# slapcie.net
KiCad netlist of a schematic drawn in Altium Designer
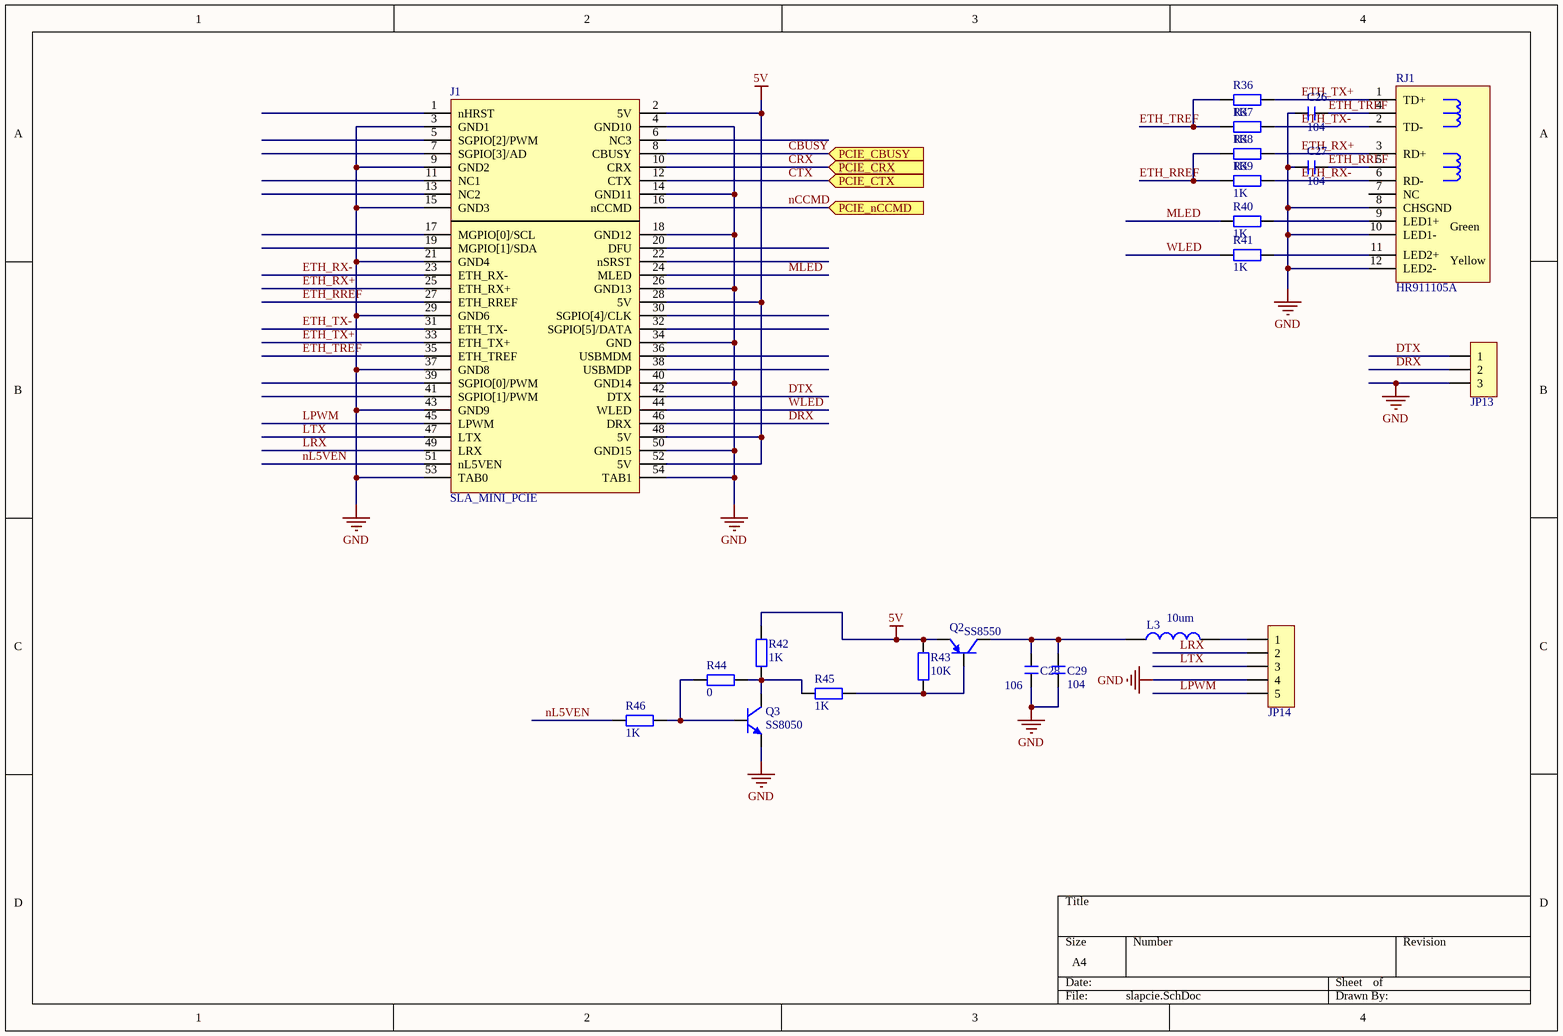
[diagram p0: slapcie.SchDoc]

(export (version "E")
  (design (tool "Eeschema 10.0.6"))
  (components
    (comp (ref "C26")
      (value "104")
      (footprint "C 0603_L")
      (description "无极性贴片电容")
      (fields (field (name "版权归属") "源创客"))
      (libsource (lib "3.1   - 电阻-电容-电感") (part "C"))
    )
    (comp (ref "C27")
      (value "104")
      (footprint "C 0603_L")
      (description "无极性贴片电容")
      (fields (field (name "版权归属") "源创客"))
      (libsource (lib "3.1   - 电阻-电容-电感") (part "C"))
    )
    (comp (ref "C28")
      (value "106")
      (footprint "C 0603_L")
      (description "无极性贴片电容")
      (fields (field (name "版权归属") "源创客"))
      (libsource (lib "3.1   - 电阻-电容-电感") (part "C"))
    )
    (comp (ref "C29")
      (value "104")
      (footprint "C 0603_L")
      (description "无极性贴片电容")
      (fields (field (name "版权归属") "源创客"))
      (libsource (lib "3.1   - 电阻-电容-电感") (part "C"))
    )
    (comp (ref "J1")
      (value "SLA_MINI_PCIE")
      (footprint "MINI_PCIE")
      (libsource (lib "元件库合集") (part "SLA_PCIE"))
    )
    (comp (ref "JP13")
      (value "HDR-1X3")
      (footprint "XH2.54-LI-3P")
      (description "3P接插件")
      (fields (field (name "版权归属") "源创客"))
      (libsource (lib "4.5   - 接插件-脚距2.54") (part "Header 3"))
    )
    (comp (ref "JP14")
      (value "HDR-1X5")
      (footprint "XH2.54-WI-5P")
      (description "5P接插件")
      (fields (field (name "版权归属") "源创客"))
      (libsource (lib "4.5   - 接插件-脚距2.54") (part "Header 5"))
    )
    (comp (ref "L3")
      (value "10um")
      (footprint "L 0805")
      (description "小功率贴片电感")
      (fields (field (name "版权归属") "源创客"))
      (libsource (lib "电阻-电容-电感") (part "L"))
    )
    (comp (ref "Q2")
      (value "SS8550")
      (footprint "SOT23-3N")
      (description "高频放大-PNP型")
      (fields (field (name "版权归属") "源创客"))
      (libsource (lib "三极管") (part "8550-SMD"))
    )
    (comp (ref "Q3")
      (value "SS8050")
      (footprint "SOT23-3N")
      (description "高频放大-NPN型")
      (fields (field (name "版权归属") "源创客"))
      (libsource (lib "三极管") (part "8050-SMD"))
    )
    (comp (ref "R36")
      (value "1K")
      (footprint "R 0603_L")
      (description "贴片电阻")
      (fields (field (name "版权归属") "源创客"))
      (libsource (lib "3.1   - 电阻-电容-电感") (part "R"))
    )
    (comp (ref "R37")
      (value "1K")
      (footprint "R 0603_L")
      (description "贴片电阻")
      (fields (field (name "版权归属") "源创客"))
      (libsource (lib "3.1   - 电阻-电容-电感") (part "R"))
    )
    (comp (ref "R38")
      (value "1K")
      (footprint "R 0603_L")
      (description "贴片电阻")
      (fields (field (name "版权归属") "源创客"))
      (libsource (lib "3.1   - 电阻-电容-电感") (part "R"))
    )
    (comp (ref "R39")
      (value "1K")
      (footprint "R 0603_L")
      (description "贴片电阻")
      (fields (field (name "版权归属") "源创客"))
      (libsource (lib "3.1   - 电阻-电容-电感") (part "R"))
    )
    (comp (ref "R40")
      (value "1K")
      (footprint "R 0603_L")
      (description "贴片电阻")
      (fields (field (name "版权归属") "源创客"))
      (libsource (lib "3.1   - 电阻-电容-电感") (part "R"))
    )
    (comp (ref "R41")
      (value "1K")
      (footprint "R 0603_L")
      (description "贴片电阻")
      (fields (field (name "版权归属") "源创客"))
      (libsource (lib "3.1   - 电阻-电容-电感") (part "R"))
    )
    (comp (ref "R42")
      (value "1K")
      (footprint "R 0603_L")
      (description "贴片电阻")
      (fields (field (name "版权归属") "源创客"))
      (libsource (lib "3.1   - 电阻-电容-电感") (part "R"))
    )
    (comp (ref "R43")
      (value "10K")
      (footprint "R 0603_L")
      (description "贴片电阻")
      (fields (field (name "版权归属") "源创客"))
      (libsource (lib "3.1   - 电阻-电容-电感") (part "R"))
    )
    (comp (ref "R44")
      (value "0")
      (footprint "R 0603_L")
      (description "贴片电阻")
      (fields (field (name "版权归属") "源创客"))
      (libsource (lib "3.1   - 电阻-电容-电感") (part "R"))
    )
    (comp (ref "R45")
      (value "1K")
      (footprint "R 0603_L")
      (description "贴片电阻")
      (fields (field (name "版权归属") "源创客"))
      (libsource (lib "3.1   - 电阻-电容-电感") (part "R"))
    )
    (comp (ref "R46")
      (value "1K")
      (footprint "R 0603_L")
      (description "贴片电阻")
      (fields (field (name "版权归属") "源创客"))
      (libsource (lib "3.1   - 电阻-电容-电感") (part "R"))
    )
    (comp (ref "RJ1")
      (value "HR911105A")
      (footprint "RJ-45A12")
      (description "带灯以太网接口")
      (fields (field (name "版权归属") "源创客"))
      (libsource (lib "接口类") (part "HR911105A"))
    )
  )
  (nets
    (net (code "1") (name "/CBUSY") (class "Default")
      (node (ref "J1") (pin "8") (pinfunction "CBUSY_8") (pintype "passive"))
    )
    (net (code "2") (name "/CRX") (class "Default")
      (node (ref "J1") (pin "10") (pinfunction "CRX_10") (pintype "passive"))
    )
    (net (code "3") (name "/CTX") (class "Default")
      (node (ref "J1") (pin "12") (pinfunction "CTX_12") (pintype "passive"))
    )
    (net (code "4") (name "/DRX") (class "Default")
      (node (ref "J1") (pin "46") (pinfunction "DRX_46") (pintype "passive"))
      (node (ref "JP13") (pin "2") (pinfunction "2_2") (pintype "passive"))
    )
    (net (code "5") (name "/DTX") (class "Default")
      (node (ref "J1") (pin "42") (pinfunction "DTX_42") (pintype "passive"))
      (node (ref "JP13") (pin "1") (pinfunction "1_1") (pintype "passive"))
    )
    (net (code "6") (name "/ETH_RREF") (class "Default")
      (node (ref "C27") (pin "2") (pinfunction "2_2") (pintype "passive"))
      (node (ref "J1") (pin "27") (pinfunction "ETH_RREF_27") (pintype "passive"))
      (node (ref "R38") (pin "1") (pinfunction "1_1") (pintype "passive"))
      (node (ref "R39") (pin "1") (pinfunction "1_1") (pintype "passive"))
      (node (ref "RJ1") (pin "5") (pintype "passive"))
    )
    (net (code "7") (name "/ETH_RX+") (class "Default")
      (node (ref "J1") (pin "25") (pinfunction "ETH_RX+_25") (pintype "passive"))
      (node (ref "R38") (pin "2") (pinfunction "2_2") (pintype "passive"))
      (node (ref "RJ1") (pin "3") (pinfunction "RD+_3") (pintype "passive"))
    )
    (net (code "8") (name "/ETH_RX-") (class "Default")
      (node (ref "J1") (pin "23") (pinfunction "ETH_RX-_23") (pintype "passive"))
      (node (ref "R39") (pin "2") (pinfunction "2_2") (pintype "passive"))
      (node (ref "RJ1") (pin "6") (pinfunction "RD-_6") (pintype "passive"))
    )
    (net (code "9") (name "/ETH_TREF") (class "Default")
      (node (ref "C26") (pin "2") (pinfunction "2_2") (pintype "passive"))
      (node (ref "J1") (pin "35") (pinfunction "ETH_TREF_35") (pintype "passive"))
      (node (ref "R36") (pin "1") (pinfunction "1_1") (pintype "passive"))
      (node (ref "R37") (pin "1") (pinfunction "1_1") (pintype "passive"))
      (node (ref "RJ1") (pin "4") (pintype "passive"))
    )
    (net (code "10") (name "/ETH_TX+") (class "Default")
      (node (ref "J1") (pin "33") (pinfunction "ETH_TX+_33") (pintype "passive"))
      (node (ref "R36") (pin "2") (pinfunction "2_2") (pintype "passive"))
      (node (ref "RJ1") (pin "1") (pinfunction "TD+_1") (pintype "passive"))
    )
    (net (code "11") (name "/ETH_TX-") (class "Default")
      (node (ref "J1") (pin "31") (pinfunction "ETH_TX-_31") (pintype "passive"))
      (node (ref "R37") (pin "2") (pinfunction "2_2") (pintype "passive"))
      (node (ref "RJ1") (pin "2") (pinfunction "TD-_2") (pintype "passive"))
    )
    (net (code "12") (name "/LPWM") (class "Default")
      (node (ref "J1") (pin "45") (pinfunction "LPWM_45") (pintype "passive"))
      (node (ref "JP14") (pin "5") (pinfunction "5_5") (pintype "passive"))
    )
    (net (code "13") (name "/LRX") (class "Default")
      (node (ref "J1") (pin "49") (pinfunction "LRX_49") (pintype "passive"))
      (node (ref "JP14") (pin "2") (pinfunction "2_2") (pintype "passive"))
    )
    (net (code "14") (name "/LTX") (class "Default")
      (node (ref "J1") (pin "47") (pinfunction "LTX_47") (pintype "passive"))
      (node (ref "JP14") (pin "3") (pinfunction "3_3") (pintype "passive"))
    )
    (net (code "15") (name "/MLED") (class "Default")
      (node (ref "J1") (pin "24") (pinfunction "MLED_24") (pintype "passive"))
      (node (ref "R40") (pin "1") (pinfunction "1_1") (pintype "passive"))
    )
    (net (code "16") (name "/WLED") (class "Default")
      (node (ref "J1") (pin "44") (pinfunction "WLED_44") (pintype "passive"))
      (node (ref "R41") (pin "1") (pinfunction "1_1") (pintype "passive"))
    )
    (net (code "17") (name "/nCCMD") (class "Default")
      (node (ref "J1") (pin "16") (pinfunction "nCCMD_16") (pintype "passive"))
    )
    (net (code "18") (name "/nL5VEN") (class "Default")
      (node (ref "J1") (pin "51") (pinfunction "nL5VEN_51") (pintype "passive"))
      (node (ref "R46") (pin "1") (pinfunction "1_1") (pintype "passive"))
    )
    (net (code "19") (name "5V") (class "Default")
      (node (ref "J1") (pin "2") (pinfunction "5V_2") (pintype "passive"))
      (node (ref "J1") (pin "28") (pinfunction "5V_28") (pintype "passive"))
      (node (ref "J1") (pin "48") (pinfunction "5V_48") (pintype "passive"))
      (node (ref "J1") (pin "52") (pinfunction "5V_52") (pintype "passive"))
      (node (ref "Q2") (pin "2") (pinfunction "E_2") (pintype "passive"))
      (node (ref "R42") (pin "2") (pinfunction "2_2") (pintype "passive"))
      (node (ref "R43") (pin "2") (pinfunction "2_2") (pintype "passive"))
    )
    (net (code "20") (name "GND") (class "Default")
      (node (ref "C26") (pin "1") (pinfunction "1_1") (pintype "passive"))
      (node (ref "C27") (pin "1") (pinfunction "1_1") (pintype "passive"))
      (node (ref "C28") (pin "1") (pinfunction "1_1") (pintype "passive"))
      (node (ref "C29") (pin "2") (pinfunction "2_2") (pintype "passive"))
      (node (ref "J1") (pin "14") (pinfunction "GND11_14") (pintype "passive"))
      (node (ref "J1") (pin "15") (pinfunction "GND3_15") (pintype "passive"))
      (node (ref "J1") (pin "18") (pinfunction "GND12_18") (pintype "passive"))
      (node (ref "J1") (pin "21") (pinfunction "GND4_21") (pintype "passive"))
      (node (ref "J1") (pin "26") (pinfunction "GND13_26") (pintype "passive"))
      (node (ref "J1") (pin "29") (pinfunction "GND6_29") (pintype "passive"))
      (node (ref "J1") (pin "3") (pinfunction "GND1_3") (pintype "passive"))
      (node (ref "J1") (pin "34") (pinfunction "GND_34") (pintype "passive"))
      (node (ref "J1") (pin "37") (pinfunction "GND8_37") (pintype "passive"))
      (node (ref "J1") (pin "4") (pinfunction "GND10_4") (pintype "passive"))
      (node (ref "J1") (pin "40") (pinfunction "GND14_40") (pintype "passive"))
      (node (ref "J1") (pin "43") (pinfunction "GND9_43") (pintype "passive"))
      (node (ref "J1") (pin "50") (pinfunction "GND15_50") (pintype "passive"))
      (node (ref "J1") (pin "53") (pinfunction "TAB0_53") (pintype "passive"))
      (node (ref "J1") (pin "54") (pinfunction "TAB1_54") (pintype "passive"))
      (node (ref "J1") (pin "9") (pinfunction "GND2_9") (pintype "passive"))
      (node (ref "JP13") (pin "3") (pinfunction "3_3") (pintype "passive"))
      (node (ref "JP14") (pin "4") (pinfunction "4_4") (pintype "passive"))
      (node (ref "Q3") (pin "2") (pinfunction "E_2") (pintype "passive"))
      (node (ref "RJ1") (pin "10") (pinfunction "LED1-_10") (pintype "passive"))
      (node (ref "RJ1") (pin "12") (pinfunction "LED2-_12") (pintype "passive"))
      (node (ref "RJ1") (pin "8") (pinfunction "CHSGND_8") (pintype "passive"))
    )
    (net (code "21") (name "Net-(JP14-Pad1)") (class "Default")
      (node (ref "JP14") (pin "1") (pinfunction "1_1") (pintype "passive"))
      (node (ref "L3") (pin "2") (pinfunction "2_2") (pintype "passive"))
    )
    (net (code "22") (name "Net-(Q2-B)") (class "Default")
      (node (ref "Q2") (pin "1") (pinfunction "B_1") (pintype "passive"))
      (node (ref "R43") (pin "1") (pinfunction "1_1") (pintype "passive"))
      (node (ref "R45") (pin "2") (pinfunction "2_2") (pintype "passive"))
    )
    (net (code "23") (name "Net-(Q2-C)") (class "Default")
      (node (ref "C28") (pin "2") (pinfunction "2_2") (pintype "passive"))
      (node (ref "C29") (pin "1") (pinfunction "1_1") (pintype "passive"))
      (node (ref "L3") (pin "1") (pinfunction "1_1") (pintype "passive"))
      (node (ref "Q2") (pin "3") (pinfunction "C_3") (pintype "passive"))
    )
    (net (code "24") (name "Net-(Q3-B)") (class "Default")
      (node (ref "Q3") (pin "1") (pinfunction "B_1") (pintype "passive"))
      (node (ref "R44") (pin "1") (pinfunction "1_1") (pintype "passive"))
      (node (ref "R46") (pin "2") (pinfunction "2_2") (pintype "passive"))
    )
    (net (code "25") (name "Net-(Q3-C)") (class "Default")
      (node (ref "Q3") (pin "3") (pinfunction "C_3") (pintype "passive"))
      (node (ref "R42") (pin "1") (pinfunction "1_1") (pintype "passive"))
      (node (ref "R44") (pin "2") (pinfunction "2_2") (pintype "passive"))
      (node (ref "R45") (pin "1") (pinfunction "1_1") (pintype "passive"))
    )
    (net (code "26") (name "Net-(RJ1-LED1+)") (class "Default")
      (node (ref "R40") (pin "2") (pinfunction "2_2") (pintype "passive"))
      (node (ref "RJ1") (pin "9") (pinfunction "LED1+_9") (pintype "passive"))
    )
    (net (code "27") (name "Net-(RJ1-LED2+)") (class "Default")
      (node (ref "R41") (pin "2") (pinfunction "2_2") (pintype "passive"))
      (node (ref "RJ1") (pin "11") (pinfunction "LED2+_11") (pintype "passive"))
    )
    (net (code "28") (name "unconnected-(J1-DFU-Pad20)") (class "Default")
      (node (ref "J1") (pin "20") (pinfunction "DFU_20") (pintype "passive"))
    )
    (net (code "29") (name "unconnected-(J1-MGPIO[0]{slash}SCL-Pad17)") (class "Default")
      (node (ref "J1") (pin "17") (pinfunction "MGPIO[0]/SCL_17") (pintype "passive"))
    )
    (net (code "30") (name "unconnected-(J1-MGPIO[1]{slash}SDA-Pad19)") (class "Default")
      (node (ref "J1") (pin "19") (pinfunction "MGPIO[1]/SDA_19") (pintype "passive"))
    )
    (net (code "31") (name "unconnected-(J1-NC1-Pad11)") (class "Default")
      (node (ref "J1") (pin "11") (pinfunction "NC1_11") (pintype "passive"))
    )
    (net (code "32") (name "unconnected-(J1-NC2-Pad13)") (class "Default")
      (node (ref "J1") (pin "13") (pinfunction "NC2_13") (pintype "passive"))
    )
    (net (code "33") (name "unconnected-(J1-NC3-Pad6)") (class "Default")
      (node (ref "J1") (pin "6") (pinfunction "NC3_6") (pintype "passive"))
    )
    (net (code "34") (name "unconnected-(J1-SGPIO[0]{slash}PWM-Pad39)") (class "Default")
      (node (ref "J1") (pin "39") (pinfunction "SGPIO[0]/PWM_39") (pintype "passive"))
    )
    (net (code "35") (name "unconnected-(J1-SGPIO[1]{slash}PWM-Pad41)") (class "Default")
      (node (ref "J1") (pin "41") (pinfunction "SGPIO[1]/PWM_41") (pintype "passive"))
    )
    (net (code "36") (name "unconnected-(J1-SGPIO[2]{slash}PWM-Pad5)") (class "Default")
      (node (ref "J1") (pin "5") (pinfunction "SGPIO[2]/PWM_5") (pintype "passive"))
    )
    (net (code "37") (name "unconnected-(J1-SGPIO[3]{slash}AD-Pad7)") (class "Default")
      (node (ref "J1") (pin "7") (pinfunction "SGPIO[3]/AD_7") (pintype "passive"))
    )
    (net (code "38") (name "unconnected-(J1-SGPIO[4]{slash}CLK-Pad30)") (class "Default")
      (node (ref "J1") (pin "30") (pinfunction "SGPIO[4]/CLK_30") (pintype "passive"))
    )
    (net (code "39") (name "unconnected-(J1-SGPIO[5]{slash}DATA-Pad32)") (class "Default")
      (node (ref "J1") (pin "32") (pinfunction "SGPIO[5]/DATA_32") (pintype "passive"))
    )
    (net (code "40") (name "unconnected-(J1-USBMDM-Pad36)") (class "Default")
      (node (ref "J1") (pin "36") (pinfunction "USBMDM_36") (pintype "passive"))
    )
    (net (code "41") (name "unconnected-(J1-USBMDP-Pad38)") (class "Default")
      (node (ref "J1") (pin "38") (pinfunction "USBMDP_38") (pintype "passive"))
    )
    (net (code "42") (name "unconnected-(J1-nHRST-Pad1)") (class "Default")
      (node (ref "J1") (pin "1") (pinfunction "nHRST_1") (pintype "passive"))
    )
    (net (code "43") (name "unconnected-(J1-nSRST-Pad22)") (class "Default")
      (node (ref "J1") (pin "22") (pinfunction "nSRST_22") (pintype "passive"))
    )
    (net (code "44") (name "unconnected-(RJ1-NC-Pad7)") (class "Default")
      (node (ref "RJ1") (pin "7") (pinfunction "NC_7") (pintype "passive"))
    )
  )
)
